# Light_Sensor_Layout.net
KiCad netlist of a schematic drawn in EAGLE
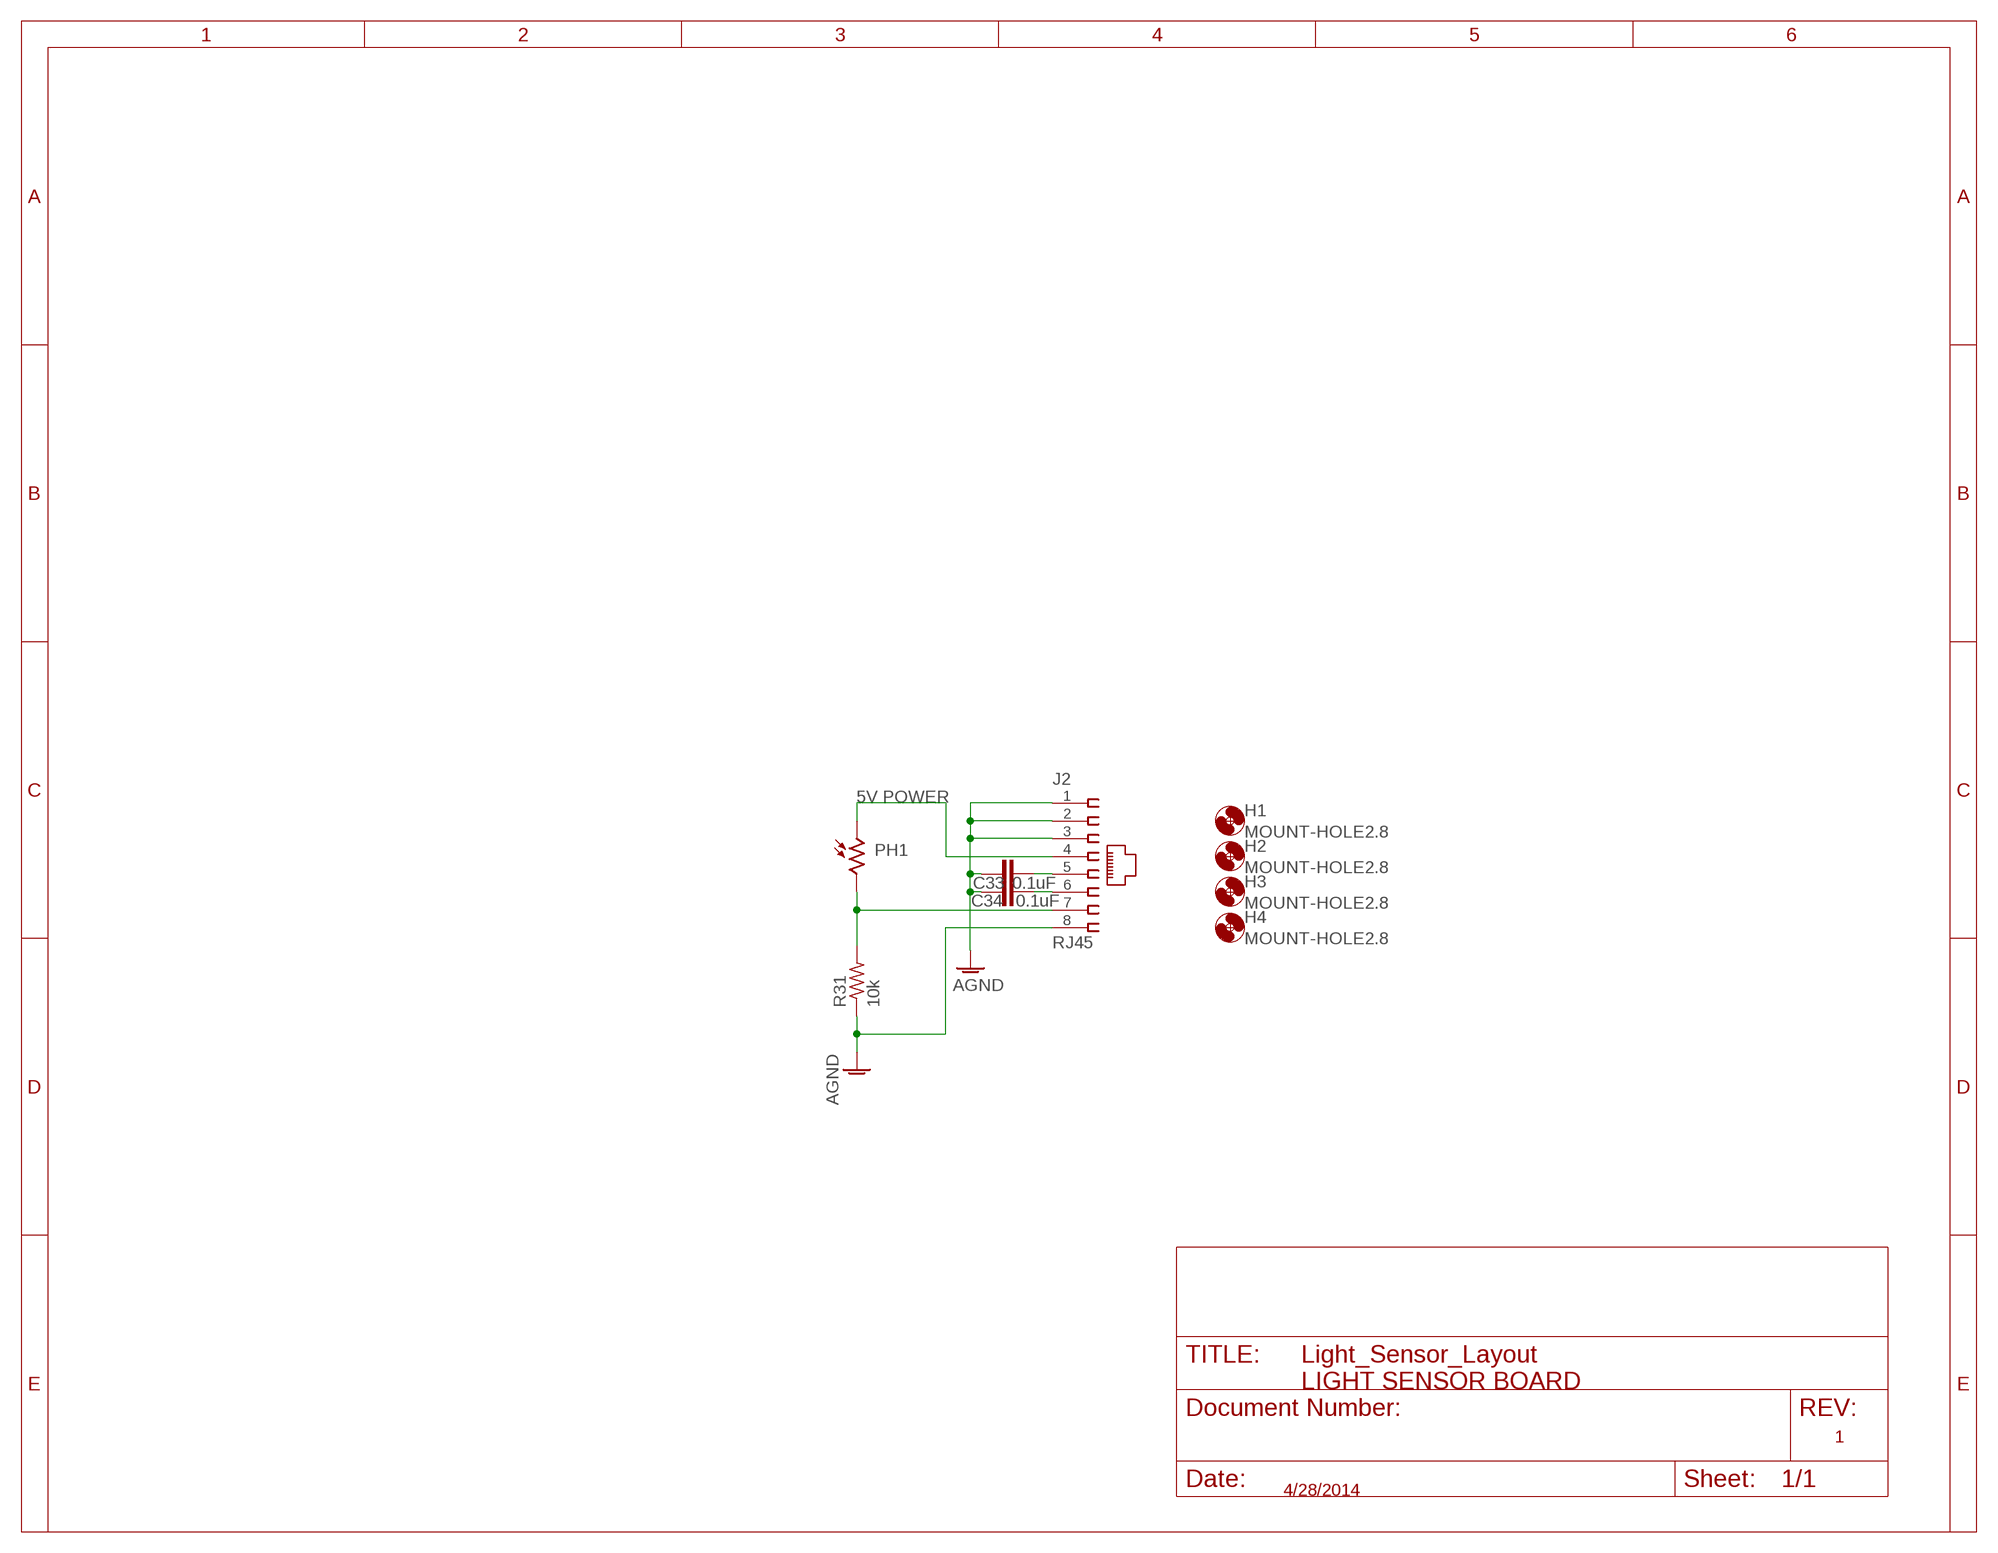
[diagram p0: schematic, sheet 1]

(export (version "E")
  (design (tool "Eeschema 10.0.6"))
  (components
    (comp (ref "C33")
      (value "0.1uF")
      (footprint "eagle-import:C0603K")
      (libsource (lib "eagle-import") (part "C-EUC0603K"))
    )
    (comp (ref "C34")
      (value "0.1uF")
      (footprint "eagle-import:C0603K")
      (libsource (lib "eagle-import") (part "C-EUC0603K"))
    )
    (comp (ref "H1")
      (value "MOUNT-HOLE2.8")
      (footprint "eagle-import:2,8")
      (libsource (lib "eagle-import") (part "MOUNT-HOLE2.8"))
    )
    (comp (ref "H2")
      (value "MOUNT-HOLE2.8")
      (footprint "eagle-import:2,8")
      (libsource (lib "eagle-import") (part "MOUNT-HOLE2.8"))
    )
    (comp (ref "H3")
      (value "MOUNT-HOLE2.8")
      (footprint "eagle-import:2,8")
      (libsource (lib "eagle-import") (part "MOUNT-HOLE2.8"))
    )
    (comp (ref "H4")
      (value "MOUNT-HOLE2.8")
      (footprint "eagle-import:2,8")
      (libsource (lib "eagle-import") (part "MOUNT-HOLE2.8"))
    )
    (comp (ref "J2")
      (value "RJ45")
      (footprint "eagle-import:555167-1")
      (libsource (lib "eagle-import") (part "555167-1"))
    )
    (comp (ref "PH1")
      (value "VT90N2")
      (footprint "eagle-import:VT900")
      (libsource (lib "eagle-import") (part "VT90N2"))
    )
    (comp (ref "R31")
      (value "10k")
      (footprint "eagle-import:R1206")
      (libsource (lib "eagle-import") (part "R-US_R1206"))
    )
  )
  (nets
    (net (code "1") (name "AGND") (class "Default")
      (node (ref "C33") (pin "1") (pinfunction "1_1") (pintype "passive"))
      (node (ref "C34") (pin "1") (pinfunction "1_1") (pintype "passive"))
      (node (ref "J2") (pin "1") (pinfunction "1_1") (pintype "passive"))
      (node (ref "J2") (pin "2") (pinfunction "2_2") (pintype "passive"))
      (node (ref "J2") (pin "3") (pinfunction "3_3") (pintype "passive"))
      (node (ref "J2") (pin "8") (pinfunction "8_8") (pintype "passive"))
      (node (ref "R31") (pin "1") (pinfunction "1_1") (pintype "passive"))
    )
    (net (code "2") (name "Net-(C33-Pad2)") (class "Default")
      (node (ref "C33") (pin "2") (pinfunction "2_2") (pintype "passive"))
      (node (ref "J2") (pin "5") (pinfunction "5_5") (pintype "passive"))
    )
    (net (code "3") (name "Net-(C34-Pad2)") (class "Default")
      (node (ref "C34") (pin "2") (pinfunction "2_2") (pintype "passive"))
      (node (ref "J2") (pin "6") (pinfunction "6_6") (pintype "passive"))
    )
    (net (code "4") (name "Net-(J2-Pad4)") (class "Default")
      (node (ref "J2") (pin "4") (pinfunction "4_4") (pintype "passive"))
      (node (ref "PH1") (pin "1") (pinfunction "1_1") (pintype "passive"))
    )
    (net (code "5") (name "Net-(J2-Pad7)") (class "Default")
      (node (ref "J2") (pin "7") (pinfunction "7_7") (pintype "passive"))
      (node (ref "PH1") (pin "2") (pinfunction "2_2") (pintype "passive"))
      (node (ref "R31") (pin "2") (pinfunction "2_2") (pintype "passive"))
    )
  )
)
